# RELAY16.net
KiCad netlist of a schematic drawn in EAGLE
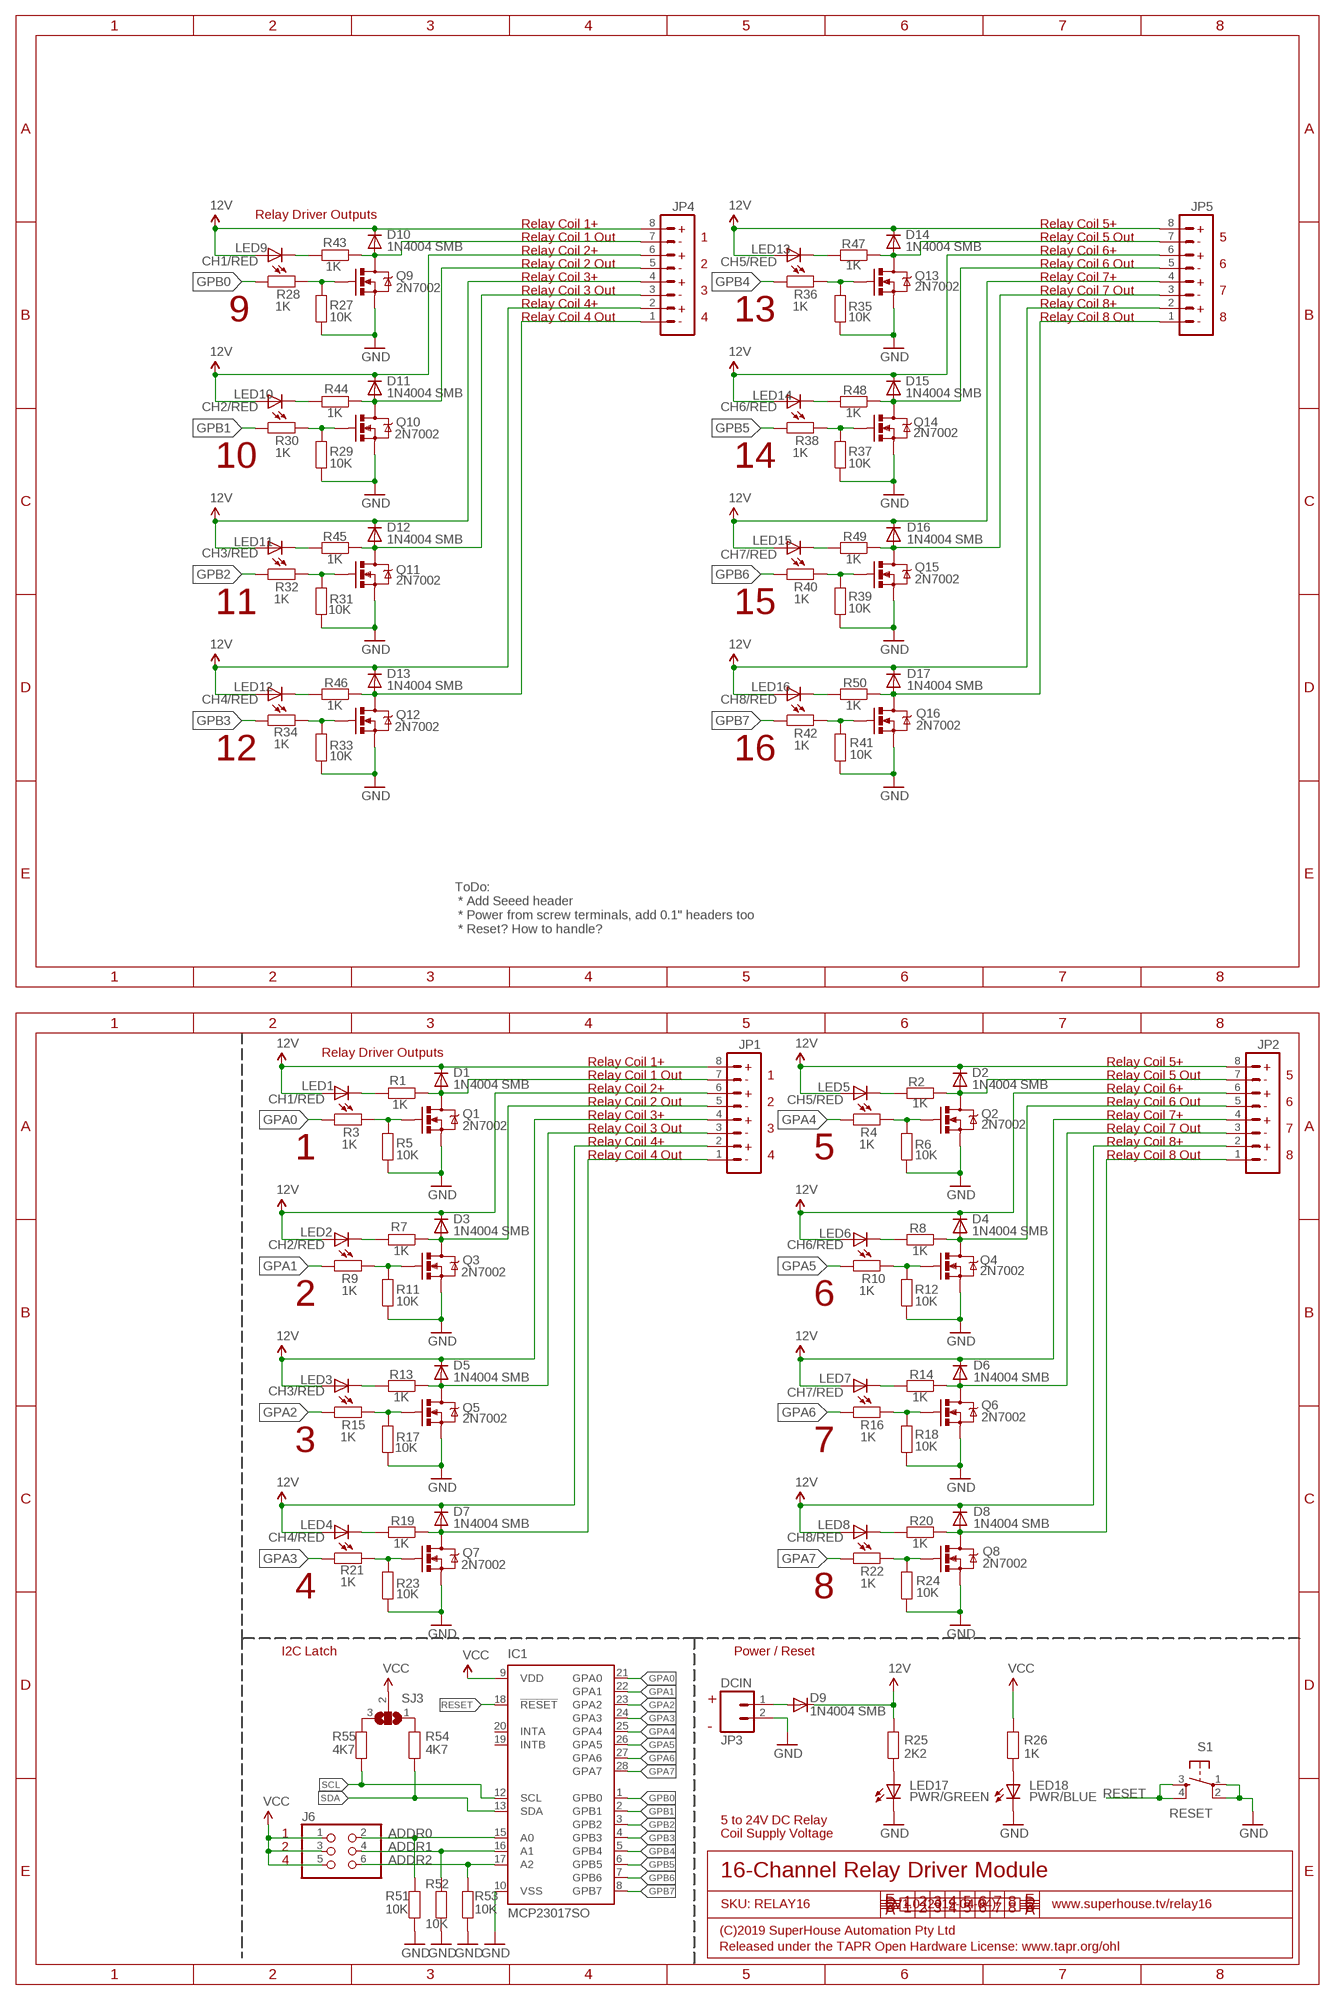
[diagram p0: schematic, sheet 1]

(export (version "E")
  (design (tool "Eeschema 10.0.6"))
  (components
    (comp (ref "D1")
      (value "1N4004 SMB")
      (footprint "eagle-import:SMB-DIODE")
      (libsource (lib "eagle-import") (part "DIODESMB"))
    )
    (comp (ref "D2")
      (value "1N4004 SMB")
      (footprint "eagle-import:SMB-DIODE")
      (libsource (lib "eagle-import") (part "DIODESMB"))
    )
    (comp (ref "D3")
      (value "1N4004 SMB")
      (footprint "eagle-import:SMB-DIODE")
      (libsource (lib "eagle-import") (part "DIODESMB"))
    )
    (comp (ref "D4")
      (value "1N4004 SMB")
      (footprint "eagle-import:SMB-DIODE")
      (libsource (lib "eagle-import") (part "DIODESMB"))
    )
    (comp (ref "D5")
      (value "1N4004 SMB")
      (footprint "eagle-import:SMB-DIODE")
      (libsource (lib "eagle-import") (part "DIODESMB"))
    )
    (comp (ref "D6")
      (value "1N4004 SMB")
      (footprint "eagle-import:SMB-DIODE")
      (libsource (lib "eagle-import") (part "DIODESMB"))
    )
    (comp (ref "D7")
      (value "1N4004 SMB")
      (footprint "eagle-import:SMB-DIODE")
      (libsource (lib "eagle-import") (part "DIODESMB"))
    )
    (comp (ref "D8")
      (value "1N4004 SMB")
      (footprint "eagle-import:SMB-DIODE")
      (libsource (lib "eagle-import") (part "DIODESMB"))
    )
    (comp (ref "D9")
      (value "1N4004 SMB")
      (footprint "eagle-import:SMB-DIODE")
      (libsource (lib "eagle-import") (part "DIODESMB"))
    )
    (comp (ref "D10")
      (value "1N4004 SMB")
      (footprint "eagle-import:SMB-DIODE")
      (libsource (lib "eagle-import") (part "DIODESMB"))
    )
    (comp (ref "D11")
      (value "1N4004 SMB")
      (footprint "eagle-import:SMB-DIODE")
      (libsource (lib "eagle-import") (part "DIODESMB"))
    )
    (comp (ref "D12")
      (value "1N4004 SMB")
      (footprint "eagle-import:SMB-DIODE")
      (libsource (lib "eagle-import") (part "DIODESMB"))
    )
    (comp (ref "D13")
      (value "1N4004 SMB")
      (footprint "eagle-import:SMB-DIODE")
      (libsource (lib "eagle-import") (part "DIODESMB"))
    )
    (comp (ref "D14")
      (value "1N4004 SMB")
      (footprint "eagle-import:SMB-DIODE")
      (libsource (lib "eagle-import") (part "DIODESMB"))
    )
    (comp (ref "D15")
      (value "1N4004 SMB")
      (footprint "eagle-import:SMB-DIODE")
      (libsource (lib "eagle-import") (part "DIODESMB"))
    )
    (comp (ref "D16")
      (value "1N4004 SMB")
      (footprint "eagle-import:SMB-DIODE")
      (libsource (lib "eagle-import") (part "DIODESMB"))
    )
    (comp (ref "D17")
      (value "1N4004 SMB")
      (footprint "eagle-import:SMB-DIODE")
      (libsource (lib "eagle-import") (part "DIODESMB"))
    )
    (comp (ref "IC1")
      (value "MCP23017SO")
      (footprint "eagle-import:SO28W")
      (libsource (lib "eagle-import") (part "MCP23017SO"))
    )
    (comp (ref "J6")
      (value "PINHD-2X3")
      (footprint "eagle-import:2X03")
      (libsource (lib "eagle-import") (part "PINHD-2X3"))
    )
    (comp (ref "JP1")
      (value "M08")
      (footprint "eagle-import:TERMINALBLOCK_3.5MM_8")
      (libsource (lib "eagle-import") (part "M08"))
    )
    (comp (ref "JP2")
      (value "M08")
      (footprint "eagle-import:TERMINALBLOCK_3.5MM_8")
      (libsource (lib "eagle-import") (part "M08"))
    )
    (comp (ref "JP3")
      (value "DCIN")
      (footprint "eagle-import:SCREWTERMINAL-3.5MM-2")
      (libsource (lib "eagle-import") (part "M023.5MM"))
    )
    (comp (ref "JP4")
      (value "M08")
      (footprint "eagle-import:TERMINALBLOCK_3.5MM_8")
      (libsource (lib "eagle-import") (part "M08"))
    )
    (comp (ref "JP5")
      (value "M08")
      (footprint "eagle-import:TERMINALBLOCK_3.5MM_8")
      (libsource (lib "eagle-import") (part "M08"))
    )
    (comp (ref "LED1")
      (value "CH1/RED")
      (footprint "eagle-import:LED-0603")
      (libsource (lib "eagle-import") (part "LED0603"))
    )
    (comp (ref "LED2")
      (value "CH2/RED")
      (footprint "eagle-import:LED-0603")
      (libsource (lib "eagle-import") (part "LED0603"))
    )
    (comp (ref "LED3")
      (value "CH3/RED")
      (footprint "eagle-import:LED-0603")
      (libsource (lib "eagle-import") (part "LED0603"))
    )
    (comp (ref "LED4")
      (value "CH4/RED")
      (footprint "eagle-import:LED-0603")
      (libsource (lib "eagle-import") (part "LED0603"))
    )
    (comp (ref "LED5")
      (value "CH5/RED")
      (footprint "eagle-import:LED-0603")
      (libsource (lib "eagle-import") (part "LED0603"))
    )
    (comp (ref "LED6")
      (value "CH6/RED")
      (footprint "eagle-import:LED-0603")
      (libsource (lib "eagle-import") (part "LED0603"))
    )
    (comp (ref "LED7")
      (value "CH7/RED")
      (footprint "eagle-import:LED-0603")
      (libsource (lib "eagle-import") (part "LED0603"))
    )
    (comp (ref "LED8")
      (value "CH8/RED")
      (footprint "eagle-import:LED-0603")
      (libsource (lib "eagle-import") (part "LED0603"))
    )
    (comp (ref "LED9")
      (value "CH1/RED")
      (footprint "eagle-import:LED-0603")
      (libsource (lib "eagle-import") (part "LED0603"))
    )
    (comp (ref "LED10")
      (value "CH2/RED")
      (footprint "eagle-import:LED-0603")
      (libsource (lib "eagle-import") (part "LED0603"))
    )
    (comp (ref "LED11")
      (value "CH3/RED")
      (footprint "eagle-import:LED-0603")
      (libsource (lib "eagle-import") (part "LED0603"))
    )
    (comp (ref "LED12")
      (value "CH4/RED")
      (footprint "eagle-import:LED-0603")
      (libsource (lib "eagle-import") (part "LED0603"))
    )
    (comp (ref "LED13")
      (value "CH5/RED")
      (footprint "eagle-import:LED-0603")
      (libsource (lib "eagle-import") (part "LED0603"))
    )
    (comp (ref "LED14")
      (value "CH6/RED")
      (footprint "eagle-import:LED-0603")
      (libsource (lib "eagle-import") (part "LED0603"))
    )
    (comp (ref "LED15")
      (value "CH7/RED")
      (footprint "eagle-import:LED-0603")
      (libsource (lib "eagle-import") (part "LED0603"))
    )
    (comp (ref "LED16")
      (value "CH8/RED")
      (footprint "eagle-import:LED-0603")
      (libsource (lib "eagle-import") (part "LED0603"))
    )
    (comp (ref "LED17")
      (value "PWR/GREEN")
      (footprint "eagle-import:LED-0603")
      (libsource (lib "eagle-import") (part "LED0603"))
    )
    (comp (ref "LED18")
      (value "PWR/BLUE")
      (footprint "eagle-import:LED-0603")
      (libsource (lib "eagle-import") (part "LED0603"))
    )
    (comp (ref "Q1")
      (value "2N7002")
      (footprint "eagle-import:SOT23-3")
      (libsource (lib "eagle-import") (part "MOSFET-NCHANNELSMD"))
    )
    (comp (ref "Q2")
      (value "2N7002")
      (footprint "eagle-import:SOT23-3")
      (libsource (lib "eagle-import") (part "MOSFET-NCHANNELSMD"))
    )
    (comp (ref "Q3")
      (value "2N7002")
      (footprint "eagle-import:SOT23-3")
      (libsource (lib "eagle-import") (part "MOSFET-NCHANNELSMD"))
    )
    (comp (ref "Q4")
      (value "2N7002")
      (footprint "eagle-import:SOT23-3")
      (libsource (lib "eagle-import") (part "MOSFET-NCHANNELSMD"))
    )
    (comp (ref "Q5")
      (value "2N7002")
      (footprint "eagle-import:SOT23-3")
      (libsource (lib "eagle-import") (part "MOSFET-NCHANNELSMD"))
    )
    (comp (ref "Q6")
      (value "2N7002")
      (footprint "eagle-import:SOT23-3")
      (libsource (lib "eagle-import") (part "MOSFET-NCHANNELSMD"))
    )
    (comp (ref "Q7")
      (value "2N7002")
      (footprint "eagle-import:SOT23-3")
      (libsource (lib "eagle-import") (part "MOSFET-NCHANNELSMD"))
    )
    (comp (ref "Q8")
      (value "2N7002")
      (footprint "eagle-import:SOT23-3")
      (libsource (lib "eagle-import") (part "MOSFET-NCHANNELSMD"))
    )
    (comp (ref "Q9")
      (value "2N7002")
      (footprint "eagle-import:SOT23-3")
      (libsource (lib "eagle-import") (part "MOSFET-NCHANNELSMD"))
    )
    (comp (ref "Q10")
      (value "2N7002")
      (footprint "eagle-import:SOT23-3")
      (libsource (lib "eagle-import") (part "MOSFET-NCHANNELSMD"))
    )
    (comp (ref "Q11")
      (value "2N7002")
      (footprint "eagle-import:SOT23-3")
      (libsource (lib "eagle-import") (part "MOSFET-NCHANNELSMD"))
    )
    (comp (ref "Q12")
      (value "2N7002")
      (footprint "eagle-import:SOT23-3")
      (libsource (lib "eagle-import") (part "MOSFET-NCHANNELSMD"))
    )
    (comp (ref "Q13")
      (value "2N7002")
      (footprint "eagle-import:SOT23-3")
      (libsource (lib "eagle-import") (part "MOSFET-NCHANNELSMD"))
    )
    (comp (ref "Q14")
      (value "2N7002")
      (footprint "eagle-import:SOT23-3")
      (libsource (lib "eagle-import") (part "MOSFET-NCHANNELSMD"))
    )
    (comp (ref "Q15")
      (value "2N7002")
      (footprint "eagle-import:SOT23-3")
      (libsource (lib "eagle-import") (part "MOSFET-NCHANNELSMD"))
    )
    (comp (ref "Q16")
      (value "2N7002")
      (footprint "eagle-import:SOT23-3")
      (libsource (lib "eagle-import") (part "MOSFET-NCHANNELSMD"))
    )
    (comp (ref "R1")
      (value "1K")
      (footprint "eagle-import:0603")
      (libsource (lib "eagle-import") (part "RESISTOR0603"))
    )
    (comp (ref "R2")
      (value "1K")
      (footprint "eagle-import:0603")
      (libsource (lib "eagle-import") (part "RESISTOR0603"))
    )
    (comp (ref "R3")
      (value "1K")
      (footprint "eagle-import:0603")
      (libsource (lib "eagle-import") (part "RESISTOR0603"))
    )
    (comp (ref "R4")
      (value "1K")
      (footprint "eagle-import:0603")
      (libsource (lib "eagle-import") (part "RESISTOR0603"))
    )
    (comp (ref "R5")
      (value "10K")
      (footprint "eagle-import:0603")
      (libsource (lib "eagle-import") (part "RESISTOR0603"))
    )
    (comp (ref "R6")
      (value "10K")
      (footprint "eagle-import:0603")
      (libsource (lib "eagle-import") (part "RESISTOR0603"))
    )
    (comp (ref "R7")
      (value "1K")
      (footprint "eagle-import:0603")
      (libsource (lib "eagle-import") (part "RESISTOR0603"))
    )
    (comp (ref "R8")
      (value "1K")
      (footprint "eagle-import:0603")
      (libsource (lib "eagle-import") (part "RESISTOR0603"))
    )
    (comp (ref "R9")
      (value "1K")
      (footprint "eagle-import:0603")
      (libsource (lib "eagle-import") (part "RESISTOR0603"))
    )
    (comp (ref "R10")
      (value "1K")
      (footprint "eagle-import:0603")
      (libsource (lib "eagle-import") (part "RESISTOR0603"))
    )
    (comp (ref "R11")
      (value "10K")
      (footprint "eagle-import:0603")
      (libsource (lib "eagle-import") (part "RESISTOR0603"))
    )
    (comp (ref "R12")
      (value "10K")
      (footprint "eagle-import:0603")
      (libsource (lib "eagle-import") (part "RESISTOR0603"))
    )
    (comp (ref "R13")
      (value "1K")
      (footprint "eagle-import:0603")
      (libsource (lib "eagle-import") (part "RESISTOR0603"))
    )
    (comp (ref "R14")
      (value "1K")
      (footprint "eagle-import:0603")
      (libsource (lib "eagle-import") (part "RESISTOR0603"))
    )
    (comp (ref "R15")
      (value "1K")
      (footprint "eagle-import:0603")
      (libsource (lib "eagle-import") (part "RESISTOR0603"))
    )
    (comp (ref "R16")
      (value "1K")
      (footprint "eagle-import:0603")
      (libsource (lib "eagle-import") (part "RESISTOR0603"))
    )
    (comp (ref "R17")
      (value "10K")
      (footprint "eagle-import:0603")
      (libsource (lib "eagle-import") (part "RESISTOR0603"))
    )
    (comp (ref "R18")
      (value "10K")
      (footprint "eagle-import:0603")
      (libsource (lib "eagle-import") (part "RESISTOR0603"))
    )
    (comp (ref "R19")
      (value "1K")
      (footprint "eagle-import:0603")
      (libsource (lib "eagle-import") (part "RESISTOR0603"))
    )
    (comp (ref "R20")
      (value "1K")
      (footprint "eagle-import:0603")
      (libsource (lib "eagle-import") (part "RESISTOR0603"))
    )
    (comp (ref "R21")
      (value "1K")
      (footprint "eagle-import:0603")
      (libsource (lib "eagle-import") (part "RESISTOR0603"))
    )
    (comp (ref "R22")
      (value "1K")
      (footprint "eagle-import:0603")
      (libsource (lib "eagle-import") (part "RESISTOR0603"))
    )
    (comp (ref "R23")
      (value "10K")
      (footprint "eagle-import:0603")
      (libsource (lib "eagle-import") (part "RESISTOR0603"))
    )
    (comp (ref "R24")
      (value "10K")
      (footprint "eagle-import:0603")
      (libsource (lib "eagle-import") (part "RESISTOR0603"))
    )
    (comp (ref "R25")
      (value "2K2")
      (footprint "eagle-import:0603")
      (libsource (lib "eagle-import") (part "RESISTOR0603"))
    )
    (comp (ref "R26")
      (value "1K")
      (footprint "eagle-import:0603")
      (libsource (lib "eagle-import") (part "RESISTOR0603"))
    )
    (comp (ref "R27")
      (value "10K")
      (footprint "eagle-import:0603")
      (libsource (lib "eagle-import") (part "RESISTOR0603"))
    )
    (comp (ref "R28")
      (value "1K")
      (footprint "eagle-import:0603")
      (libsource (lib "eagle-import") (part "RESISTOR0603"))
    )
    (comp (ref "R29")
      (value "10K")
      (footprint "eagle-import:0603")
      (libsource (lib "eagle-import") (part "RESISTOR0603"))
    )
    (comp (ref "R30")
      (value "1K")
      (footprint "eagle-import:0603")
      (libsource (lib "eagle-import") (part "RESISTOR0603"))
    )
    (comp (ref "R31")
      (value "10K")
      (footprint "eagle-import:0603")
      (libsource (lib "eagle-import") (part "RESISTOR0603"))
    )
    (comp (ref "R32")
      (value "1K")
      (footprint "eagle-import:0603")
      (libsource (lib "eagle-import") (part "RESISTOR0603"))
    )
    (comp (ref "R33")
      (value "10K")
      (footprint "eagle-import:0603")
      (libsource (lib "eagle-import") (part "RESISTOR0603"))
    )
    (comp (ref "R34")
      (value "1K")
      (footprint "eagle-import:0603")
      (libsource (lib "eagle-import") (part "RESISTOR0603"))
    )
    (comp (ref "R35")
      (value "10K")
      (footprint "eagle-import:0603")
      (libsource (lib "eagle-import") (part "RESISTOR0603"))
    )
    (comp (ref "R36")
      (value "1K")
      (footprint "eagle-import:0603")
      (libsource (lib "eagle-import") (part "RESISTOR0603"))
    )
    (comp (ref "R37")
      (value "10K")
      (footprint "eagle-import:0603")
      (libsource (lib "eagle-import") (part "RESISTOR0603"))
    )
    (comp (ref "R38")
      (value "1K")
      (footprint "eagle-import:0603")
      (libsource (lib "eagle-import") (part "RESISTOR0603"))
    )
    (comp (ref "R39")
      (value "10K")
      (footprint "eagle-import:0603")
      (libsource (lib "eagle-import") (part "RESISTOR0603"))
    )
    (comp (ref "R40")
      (value "1K")
      (footprint "eagle-import:0603")
      (libsource (lib "eagle-import") (part "RESISTOR0603"))
    )
    (comp (ref "R41")
      (value "10K")
      (footprint "eagle-import:0603")
      (libsource (lib "eagle-import") (part "RESISTOR0603"))
    )
    (comp (ref "R42")
      (value "1K")
      (footprint "eagle-import:0603")
      (libsource (lib "eagle-import") (part "RESISTOR0603"))
    )
    (comp (ref "R43")
      (value "1K")
      (footprint "eagle-import:0603")
      (libsource (lib "eagle-import") (part "RESISTOR0603"))
    )
    (comp (ref "R44")
      (value "1K")
      (footprint "eagle-import:0603")
      (libsource (lib "eagle-import") (part "RESISTOR0603"))
    )
    (comp (ref "R45")
      (value "1K")
      (footprint "eagle-import:0603")
      (libsource (lib "eagle-import") (part "RESISTOR0603"))
    )
    (comp (ref "R46")
      (value "1K")
      (footprint "eagle-import:0603")
      (libsource (lib "eagle-import") (part "RESISTOR0603"))
    )
    (comp (ref "R47")
      (value "1K")
      (footprint "eagle-import:0603")
      (libsource (lib "eagle-import") (part "RESISTOR0603"))
    )
    (comp (ref "R48")
      (value "1K")
      (footprint "eagle-import:0603")
      (libsource (lib "eagle-import") (part "RESISTOR0603"))
    )
    (comp (ref "R49")
      (value "1K")
      (footprint "eagle-import:0603")
      (libsource (lib "eagle-import") (part "RESISTOR0603"))
    )
    (comp (ref "R50")
      (value "1K")
      (footprint "eagle-import:0603")
      (libsource (lib "eagle-import") (part "RESISTOR0603"))
    )
    (comp (ref "R51")
      (value "10K")
      (footprint "eagle-import:0603")
      (libsource (lib "eagle-import") (part "RESISTOR0603"))
    )
    (comp (ref "R52")
      (value "10K")
      (footprint "eagle-import:0603")
      (libsource (lib "eagle-import") (part "RESISTOR0603"))
    )
    (comp (ref "R53")
      (value "10K")
      (footprint "eagle-import:0603")
      (libsource (lib "eagle-import") (part "RESISTOR0603"))
    )
    (comp (ref "R54")
      (value "4K7")
      (footprint "eagle-import:0603")
      (libsource (lib "eagle-import") (part "RESISTOR0603"))
    )
    (comp (ref "R55")
      (value "4K7")
      (footprint "eagle-import:0603")
      (libsource (lib "eagle-import") (part "RESISTOR0603"))
    )
    (comp (ref "S1")
      (value "RESET")
      (footprint "eagle-import:TACTILE_SWITCH_SMD")
      (libsource (lib "eagle-import") (part "TAC_SWITCHSMD"))
    )
    (comp (ref "SJ3")
      (value "SJ2W")
      (footprint "eagle-import:SJ_2")
      (libsource (lib "eagle-import") (part "SJ2W"))
    )
  )
  (nets
    (net (code "1") (name "/ADDR0") (class "Default")
      (node (ref "IC1") (pin "15") (pinfunction "A0_15") (pintype "input"))
      (node (ref "J6") (pin "2") (pinfunction "2_2") (pintype "passive"))
      (node (ref "R51") (pin "2") (pinfunction "2_2") (pintype "passive"))
    )
    (net (code "2") (name "/ADDR1") (class "Default")
      (node (ref "IC1") (pin "16") (pinfunction "A1_16") (pintype "input"))
      (node (ref "J6") (pin "4") (pinfunction "4_4") (pintype "passive"))
      (node (ref "R52") (pin "2") (pinfunction "2_2") (pintype "passive"))
    )
    (net (code "3") (name "/ADDR2") (class "Default")
      (node (ref "IC1") (pin "17") (pinfunction "A2_17") (pintype "input"))
      (node (ref "J6") (pin "6") (pinfunction "6_6") (pintype "passive"))
      (node (ref "R53") (pin "2") (pinfunction "2_2") (pintype "passive"))
    )
    (net (code "4") (name "12V") (class "Default")
      (node (ref "D1") (pin "C") (pinfunction "C_C") (pintype "passive"))
      (node (ref "D10") (pin "C") (pinfunction "C_C") (pintype "passive"))
      (node (ref "D11") (pin "C") (pinfunction "C_C") (pintype "passive"))
      (node (ref "D12") (pin "C") (pinfunction "C_C") (pintype "passive"))
      (node (ref "D13") (pin "C") (pinfunction "C_C") (pintype "passive"))
      (node (ref "D14") (pin "C") (pinfunction "C_C") (pintype "passive"))
      (node (ref "D15") (pin "C") (pinfunction "C_C") (pintype "passive"))
      (node (ref "D16") (pin "C") (pinfunction "C_C") (pintype "passive"))
      (node (ref "D17") (pin "C") (pinfunction "C_C") (pintype "passive"))
      (node (ref "D2") (pin "C") (pinfunction "C_C") (pintype "passive"))
      (node (ref "D3") (pin "C") (pinfunction "C_C") (pintype "passive"))
      (node (ref "D4") (pin "C") (pinfunction "C_C") (pintype "passive"))
      (node (ref "D5") (pin "C") (pinfunction "C_C") (pintype "passive"))
      (node (ref "D6") (pin "C") (pinfunction "C_C") (pintype "passive"))
      (node (ref "D7") (pin "C") (pinfunction "C_C") (pintype "passive"))
      (node (ref "D8") (pin "C") (pinfunction "C_C") (pintype "passive"))
      (node (ref "D9") (pin "C") (pinfunction "C_C") (pintype "passive"))
      (node (ref "JP1") (pin "2") (pinfunction "2_2") (pintype "passive"))
      (node (ref "JP1") (pin "4") (pinfunction "4_4") (pintype "passive"))
      (node (ref "JP1") (pin "6") (pinfunction "6_6") (pintype "passive"))
      (node (ref "JP1") (pin "8") (pinfunction "8_8") (pintype "passive"))
      (node (ref "JP2") (pin "2") (pinfunction "2_2") (pintype "passive"))
      (node (ref "JP2") (pin "4") (pinfunction "4_4") (pintype "passive"))
      (node (ref "JP2") (pin "6") (pinfunction "6_6") (pintype "passive"))
      (node (ref "JP2") (pin "8") (pinfunction "8_8") (pintype "passive"))
      (node (ref "JP4") (pin "2") (pinfunction "2_2") (pintype "passive"))
      (node (ref "JP4") (pin "4") (pinfunction "4_4") (pintype "passive"))
      (node (ref "JP4") (pin "6") (pinfunction "6_6") (pintype "passive"))
      (node (ref "JP4") (pin "8") (pinfunction "8_8") (pintype "passive"))
      (node (ref "JP5") (pin "2") (pinfunction "2_2") (pintype "passive"))
      (node (ref "JP5") (pin "4") (pinfunction "4_4") (pintype "passive"))
      (node (ref "JP5") (pin "6") (pinfunction "6_6") (pintype "passive"))
      (node (ref "JP5") (pin "8") (pinfunction "8_8") (pintype "passive"))
      (node (ref "LED1") (pin "A") (pinfunction "A_A") (pintype "passive"))
      (node (ref "LED10") (pin "A") (pinfunction "A_A") (pintype "passive"))
      (node (ref "LED11") (pin "A") (pinfunction "A_A") (pintype "passive"))
      (node (ref "LED12") (pin "A") (pinfunction "A_A") (pintype "passive"))
      (node (ref "LED13") (pin "A") (pinfunction "A_A") (pintype "passive"))
      (node (ref "LED14") (pin "A") (pinfunction "A_A") (pintype "passive"))
      (node (ref "LED15") (pin "A") (pinfunction "A_A") (pintype "passive"))
      (node (ref "LED16") (pin "A") (pinfunction "A_A") (pintype "passive"))
      (node (ref "LED2") (pin "A") (pinfunction "A_A") (pintype "passive"))
      (node (ref "LED3") (pin "A") (pinfunction "A_A") (pintype "passive"))
      (node (ref "LED4") (pin "A") (pinfunction "A_A") (pintype "passive"))
      (node (ref "LED5") (pin "A") (pinfunction "A_A") (pintype "passive"))
      (node (ref "LED6") (pin "A") (pinfunction "A_A") (pintype "passive"))
      (node (ref "LED7") (pin "A") (pinfunction "A_A") (pintype "passive"))
      (node (ref "LED8") (pin "A") (pinfunction "A_A") (pintype "passive"))
      (node (ref "LED9") (pin "A") (pinfunction "A_A") (pintype "passive"))
      (node (ref "R25") (pin "2") (pinfunction "2_2") (pintype "passive"))
    )
    (net (code "5") (name "GND") (class "Default")
      (node (ref "IC1") (pin "10") (pinfunction "VSS_10") (pintype "power_in"))
      (node (ref "JP3") (pin "2") (pinfunction "2_2") (pintype "passive"))
      (node (ref "LED17") (pin "C") (pinfunction "C_C") (pintype "passive"))
      (node (ref "LED18") (pin "C") (pinfunction "C_C") (pintype "passive"))
      (node (ref "Q1") (pin "2") (pinfunction "S_2") (pintype "passive"))
      (node (ref "Q10") (pin "2") (pinfunction "S_2") (pintype "passive"))
      (node (ref "Q11") (pin "2") (pinfunction "S_2") (pintype "passive"))
      (node (ref "Q12") (pin "2") (pinfunction "S_2") (pintype "passive"))
      (node (ref "Q13") (pin "2") (pinfunction "S_2") (pintype "passive"))
      (node (ref "Q14") (pin "2") (pinfunction "S_2") (pintype "passive"))
      (node (ref "Q15") (pin "2") (pinfunction "S_2") (pintype "passive"))
      (node (ref "Q16") (pin "2") (pinfunction "S_2") (pintype "passive"))
      (node (ref "Q2") (pin "2") (pinfunction "S_2") (pintype "passive"))
      (node (ref "Q3") (pin "2") (pinfunction "S_2") (pintype "passive"))
      (node (ref "Q4") (pin "2") (pinfunction "S_2") (pintype "passive"))
      (node (ref "Q5") (pin "2") (pinfunction "S_2") (pintype "passive"))
      (node (ref "Q6") (pin "2") (pinfunction "S_2") (pintype "passive"))
      (node (ref "Q7") (pin "2") (pinfunction "S_2") (pintype "passive"))
      (node (ref "Q8") (pin "2") (pinfunction "S_2") (pintype "passive"))
      (node (ref "Q9") (pin "2") (pinfunction "S_2") (pintype "passive"))
      (node (ref "R11") (pin "1") (pinfunction "1_1") (pintype "passive"))
      (node (ref "R12") (pin "1") (pinfunction "1_1") (pintype "passive"))
      (node (ref "R17") (pin "1") (pinfunction "1_1") (pintype "passive"))
      (node (ref "R18") (pin "1") (pinfunction "1_1") (pintype "passive"))
      (node (ref "R23") (pin "1") (pinfunction "1_1") (pintype "passive"))
      (node (ref "R24") (pin "1") (pinfunction "1_1") (pintype "passive"))
      (node (ref "R27") (pin "1") (pinfunction "1_1") (pintype "passive"))
      (node (ref "R29") (pin "1") (pinfunction "1_1") (pintype "passive"))
      (node (ref "R31") (pin "1") (pinfunction "1_1") (pintype "passive"))
      (node (ref "R33") (pin "1") (pinfunction "1_1") (pintype "passive"))
      (node (ref "R35") (pin "1") (pinfunction "1_1") (pintype "passive"))
      (node (ref "R37") (pin "1") (pinfunction "1_1") (pintype "passive"))
      (node (ref "R39") (pin "1") (pinfunction "1_1") (pintype "passive"))
      (node (ref "R41") (pin "1") (pinfunction "1_1") (pintype "passive"))
      (node (ref "R5") (pin "1") (pinfunction "1_1") (pintype "passive"))
      (node (ref "R51") (pin "1") (pinfunction "1_1") (pintype "passive"))
      (node (ref "R52") (pin "1") (pinfunction "1_1") (pintype "passive"))
      (node (ref "R53") (pin "1") (pinfunction "1_1") (pintype "passive"))
      (node (ref "R6") (pin "1") (pinfunction "1_1") (pintype "passive"))
      (node (ref "S1") (pin "1") (pinfunction "1_1") (pintype "passive"))
      (node (ref "S1") (pin "2") (pinfunction "2_2") (pintype "passive"))
    )
    (net (code "6") (name "GPA0") (class "Default")
      (node (ref "IC1") (pin "21") (pinfunction "GPA0_21") (pintype "bidirectional"))
      (node (ref "R3") (pin "2") (pinfunction "2_2") (pintype "passive"))
    )
    (net (code "7") (name "GPA1") (class "Default")
      (node (ref "IC1") (pin "22") (pinfunction "GPA1_22") (pintype "bidirectional"))
      (node (ref "R9") (pin "2") (pinfunction "2_2") (pintype "passive"))
    )
    (net (code "8") (name "GPA2") (class "Default")
      (node (ref "IC1") (pin "23") (pinfunction "GPA2_23") (pintype "bidirectional"))
      (node (ref "R15") (pin "2") (pinfunction "2_2") (pintype "passive"))
    )
    (net (code "9") (name "GPA3") (class "Default")
      (node (ref "IC1") (pin "24") (pinfunction "GPA3_24") (pintype "bidirectional"))
      (node (ref "R21") (pin "2") (pinfunction "2_2") (pintype "passive"))
    )
    (net (code "10") (name "GPA4") (class "Default")
      (node (ref "IC1") (pin "25") (pinfunction "GPA4_25") (pintype "bidirectional"))
      (node (ref "R4") (pin "2") (pinfunction "2_2") (pintype "passive"))
    )
    (net (code "11") (name "GPA5") (class "Default")
      (node (ref "IC1") (pin "26") (pinfunction "GPA5_26") (pintype "bidirectional"))
      (node (ref "R10") (pin "2") (pinfunction "2_2") (pintype "passive"))
    )
    (net (code "12") (name "GPA6") (class "Default")
      (node (ref "IC1") (pin "27") (pinfunction "GPA6_27") (pintype "bidirectional"))
      (node (ref "R16") (pin "2") (pinfunction "2_2") (pintype "passive"))
    )
    (net (code "13") (name "GPA7") (class "Default")
      (node (ref "IC1") (pin "28") (pinfunction "GPA7_28") (pintype "bidirectional"))
      (node (ref "R22") (pin "2") (pinfunction "2_2") (pintype "passive"))
    )
    (net (code "14") (name "GPB0") (class "Default")
      (node (ref "IC1") (pin "1") (pinfunction "GPB0_1") (pintype "bidirectional"))
      (node (ref "R28") (pin "2") (pinfunction "2_2") (pintype "passive"))
    )
    (net (code "15") (name "GPB1") (class "Default")
      (node (ref "IC1") (pin "2") (pinfunction "GPB1_2") (pintype "bidirectional"))
      (node (ref "R30") (pin "2") (pinfunction "2_2") (pintype "passive"))
    )
    (net (code "16") (name "GPB2") (class "Default")
      (node (ref "IC1") (pin "3") (pinfunction "GPB2_3") (pintype "bidirectional"))
      (node (ref "R32") (pin "2") (pinfunction "2_2") (pintype "passive"))
    )
    (net (code "17") (name "GPB3") (class "Default")
      (node (ref "IC1") (pin "4") (pinfunction "GPB3_4") (pintype "bidirectional"))
      (node (ref "R34") (pin "2") (pinfunction "2_2") (pintype "passive"))
    )
    (net (code "18") (name "GPB4") (class "Default")
      (node (ref "IC1") (pin "5") (pinfunction "GPB4_5") (pintype "bidirectional"))
      (node (ref "R36") (pin "2") (pinfunction "2_2") (pintype "passive"))
    )
    (net (code "19") (name "GPB5") (class "Default")
      (node (ref "IC1") (pin "6") (pinfunction "GPB5_6") (pintype "bidirectional"))
      (node (ref "R38") (pin "2") (pinfunction "2_2") (pintype "passive"))
    )
    (net (code "20") (name "GPB6") (class "Default")
      (node (ref "IC1") (pin "7") (pinfunction "GPB6_7") (pintype "bidirectional"))
      (node (ref "R40") (pin "2") (pinfunction "2_2") (pintype "passive"))
    )
    (net (code "21") (name "GPB7") (class "Default")
      (node (ref "IC1") (pin "8") (pinfunction "GPB7_8") (pintype "bidirectional"))
      (node (ref "R42") (pin "2") (pinfunction "2_2") (pintype "passive"))
    )
    (net (code "22") (name "Net-(D9-PadA)") (class "Default")
      (node (ref "D9") (pin "A") (pinfunction "A_A") (pintype "passive"))
      (node (ref "JP3") (pin "1") (pinfunction "1_1") (pintype "passive"))
    )
    (net (code "23") (name "Net-(LED1-PadC)") (class "Default")
      (node (ref "LED1") (pin "C") (pinfunction "C_C") (pintype "passive"))
      (node (ref "R1") (pin "1") (pinfunction "1_1") (pintype "passive"))
    )
    (net (code "24") (name "Net-(LED2-PadC)") (class "Default")
      (node (ref "LED2") (pin "C") (pinfunction "C_C") (pintype "passive"))
      (node (ref "R7") (pin "1") (pinfunction "1_1") (pintype "passive"))
    )
    (net (code "25") (name "Net-(LED3-PadC)") (class "Default")
      (node (ref "LED3") (pin "C") (pinfunction "C_C") (pintype "passive"))
      (node (ref "R13") (pin "1") (pinfunction "1_1") (pintype "passive"))
    )
    (net (code "26") (name "Net-(LED4-PadC)") (class "Default")
      (node (ref "LED4") (pin "C") (pinfunction "C_C") (pintype "passive"))
      (node (ref "R19") (pin "1") (pinfunction "1_1") (pintype "passive"))
    )
    (net (code "27") (name "Net-(LED5-PadC)") (class "Default")
      (node (ref "LED5") (pin "C") (pinfunction "C_C") (pintype "passive"))
      (node (ref "R2") (pin "1") (pinfunction "1_1") (pintype "passive"))
    )
    (net (code "28") (name "Net-(LED6-PadC)") (class "Default")
      (node (ref "LED6") (pin "C") (pinfunction "C_C") (pintype "passive"))
      (node (ref "R8") (pin "1") (pinfunction "1_1") (pintype "passive"))
    )
    (net (code "29") (name "Net-(LED7-PadC)") (class "Default")
      (node (ref "LED7") (pin "C") (pinfunction "C_C") (pintype "passive"))
      (node (ref "R14") (pin "1") (pinfunction "1_1") (pintype "passive"))
    )
    (net (code "30") (name "Net-(LED8-PadC)") (class "Default")
      (node (ref "LED8") (pin "C") (pinfunction "C_C") (pintype "passive"))
      (node (ref "R20") (pin "1") (pinfunction "1_1") (pintype "passive"))
    )
    (net (code "31") (name "Net-(LED9-PadC)") (class "Default")
      (node (ref "LED9") (pin "C") (pinfunction "C_C") (pintype "passive"))
      (node (ref "R43") (pin "1") (pinfunction "1_1") (pintype "passive"))
    )
    (net (code "32") (name "Net-(LED10-PadC)") (class "Default")
      (node (ref "LED10") (pin "C") (pinfunction "C_C") (pintype "passive"))
      (node (ref "R44") (pin "1") (pinfunction "1_1") (pintype "passive"))
    )
    (net (code "33") (name "Net-(LED11-PadC)") (class "Default")
      (node (ref "LED11") (pin "C") (pinfunction "C_C") (pintype "passive"))
      (node (ref "R45") (pin "1") (pinfunction "1_1") (pintype "passive"))
    )
    (net (code "34") (name "Net-(LED12-PadC)") (class "Default")
      (node (ref "LED12") (pin "C") (pinfunction "C_C") (pintype "passive"))
      (node (ref "R46") (pin "1") (pinfunction "1_1") (pintype "passive"))
    )
    (net (code "35") (name "Net-(LED13-PadC)") (class "Default")
      (node (ref "LED13") (pin "C") (pinfunction "C_C") (pintype "passive"))
      (node (ref "R47") (pin "1") (pinfunction "1_1") (pintype "passive"))
    )
    (net (code "36") (name "Net-(LED14-PadC)") (class "Default")
      (node (ref "LED14") (pin "C") (pinfunction "C_C") (pintype "passive"))
      (node (ref "R48") (pin "1") (pinfunction "1_1") (pintype "passive"))
    )
    (net (code "37") (name "Net-(LED15-PadC)") (class "Default")
      (node (ref "LED15") (pin "C") (pinfunction "C_C") (pintype "passive"))
      (node (ref "R49") (pin "1") (pinfunction "1_1") (pintype "passive"))
    )
    (net (code "38") (name "Net-(LED16-PadC)") (class "Default")
      (node (ref "LED16") (pin "C") (pinfunction "C_C") (pintype "passive"))
      (node (ref "R50") (pin "1") (pinfunction "1_1") (pintype "passive"))
    )
    (net (code "39") (name "Net-(LED17-PadA)") (class "Default")
      (node (ref "LED17") (pin "A") (pinfunction "A_A") (pintype "passive"))
      (node (ref "R25") (pin "1") (pinfunction "1_1") (pintype "passive"))
    )
    (net (code "40") (name "Net-(LED18-PadA)") (class "Default")
      (node (ref "LED18") (pin "A") (pinfunction "A_A") (pintype "passive"))
      (node (ref "R26") (pin "1") (pinfunction "1_1") (pintype "passive"))
    )
    (net (code "41") (name "Net-(Q1-D)") (class "Default")
      (node (ref "D1") (pin "A") (pinfunction "A_A") (pintype "passive"))
      (node (ref "JP1") (pin "7") (pinfunction "7_7") (pintype "passive"))
      (node (ref "Q1") (pin "3") (pinfunction "D_3") (pintype "passive"))
      (node (ref "R1") (pin "2") (pinfunction "2_2") (pintype "passive"))
    )
    (net (code "42") (name "Net-(Q1-G)") (class "Default")
      (node (ref "Q1") (pin "1") (pinfunction "G_1") (pintype "passive"))
      (node (ref "R3") (pin "1") (pinfunction "1_1") (pintype "passive"))
      (node (ref "R5") (pin "2") (pinfunction "2_2") (pintype "passive"))
    )
    (net (code "43") (name "Net-(Q2-D)") (class "Default")
      (node (ref "D2") (pin "A") (pinfunction "A_A") (pintype "passive"))
      (node (ref "JP2") (pin "7") (pinfunction "7_7") (pintype "passive"))
      (node (ref "Q2") (pin "3") (pinfunction "D_3") (pintype "passive"))
      (node (ref "R2") (pin "2") (pinfunction "2_2") (pintype "passive"))
    )
    (net (code "44") (name "Net-(Q2-G)") (class "Default")
      (node (ref "Q2") (pin "1") (pinfunction "G_1") (pintype "passive"))
      (node (ref "R4") (pin "1") (pinfunction "1_1") (pintype "passive"))
      (node (ref "R6") (pin "2") (pinfunction "2_2") (pintype "passive"))
    )
    (net (code "45") (name "Net-(Q3-D)") (class "Default")
      (node (ref "D3") (pin "A") (pinfunction "A_A") (pintype "passive"))
      (node (ref "JP1") (pin "5") (pinfunction "5_5") (pintype "passive"))
      (node (ref "Q3") (pin "3") (pinfunction "D_3") (pintype "passive"))
      (node (ref "R7") (pin "2") (pinfunction "2_2") (pintype "passive"))
    )
    (net (code "46") (name "Net-(Q3-G)") (class "Default")
      (node (ref "Q3") (pin "1") (pinfunction "G_1") (pintype "passive"))
      (node (ref "R11") (pin "2") (pinfunction "2_2") (pintype "passive"))
      (node (ref "R9") (pin "1") (pinfunction "1_1") (pintype "passive"))
    )
    (net (code "47") (name "Net-(Q4-D)") (class "Default")
      (node (ref "D4") (pin "A") (pinfunction "A_A") (pintype "passive"))
      (node (ref "JP2") (pin "5") (pinfunction "5_5") (pintype "passive"))
      (node (ref "Q4") (pin "3") (pinfunction "D_3") (pintype "passive"))
      (node (ref "R8") (pin "2") (pinfunction "2_2") (pintype "passive"))
    )
    (net (code "48") (name "Net-(Q4-G)") (class "Default")
      (node (ref "Q4") (pin "1") (pinfunction "G_1") (pintype "passive"))
      (node (ref "R10") (pin "1") (pinfunction "1_1") (pintype "passive"))
      (node (ref "R12") (pin "2") (pinfunction "2_2") (pintype "passive"))
    )
    (net (code "49") (name "Net-(Q5-D)") (class "Default")
      (node (ref "D5") (pin "A") (pinfunction "A_A") (pintype "passive"))
      (node (ref "JP1") (pin "3") (pinfunction "3_3") (pintype "passive"))
      (node (ref "Q5") (pin "3") (pinfunction "D_3") (pintype "passive"))
      (node (ref "R13") (pin "2") (pinfunction "2_2") (pintype "passive"))
    )
    (net (code "50") (name "Net-(Q5-G)") (class "Default")
      (node (ref "Q5") (pin "1") (pinfunction "G_1") (pintype "passive"))
      (node (ref "R15") (pin "1") (pinfunction "1_1") (pintype "passive"))
      (node (ref "R17") (pin "2") (pinfunction "2_2") (pintype "passive"))
    )
    (net (code "51") (name "Net-(Q6-D)") (class "Default")
      (node (ref "D6") (pin "A") (pinfunction "A_A") (pintype "passive"))
      (node (ref "JP2") (pin "3") (pinfunction "3_3") (pintype "passive"))
      (node (ref "Q6") (pin "3") (pinfunction "D_3") (pintype "passive"))
      (node (ref "R14") (pin "2") (pinfunction "2_2") (pintype "passive"))
    )
    (net (code "52") (name "Net-(Q6-G)") (class "Default")
      (node (ref "Q6") (pin "1") (pinfunction "G_1") (pintype "passive"))
      (node (ref "R16") (pin "1") (pinfunction "1_1") (pintype "passive"))
      (node (ref "R18") (pin "2") (pinfunction "2_2") (pintype "passive"))
    )
    (net (code "53") (name "Net-(Q7-D)") (class "Default")
      (node (ref "D7") (pin "A") (pinfunction "A_A") (pintype "passive"))
      (node (ref "JP1") (pin "1") (pinfunction "1_1") (pintype "passive"))
      (node (ref "Q7") (pin "3") (pinfunction "D_3") (pintype "passive"))
      (node (ref "R19") (pin "2") (pinfunction "2_2") (pintype "passive"))
    )
    (net (code "54") (name "Net-(Q7-G)") (class "Default")
      (node (ref "Q7") (pin "1") (pinfunction "G_1") (pintype "passive"))
      (node (ref "R21") (pin "1") (pinfunction "1_1") (pintype "passive"))
      (node (ref "R23") (pin "2") (pinfunction "2_2") (pintype "passive"))
    )
    (net (code "55") (name "Net-(Q8-D)") (class "Default")
      (node (ref "D8") (pin "A") (pinfunction "A_A") (pintype "passive"))
      (node (ref "JP2") (pin "1") (pinfunction "1_1") (pintype "passive"))
      (node (ref "Q8") (pin "3") (pinfunction "D_3") (pintype "passive"))
      (node (ref "R20") (pin "2") (pinfunction "2_2") (pintype "passive"))
    )
    (net (code "56") (name "Net-(Q8-G)") (class "Default")
      (node (ref "Q8") (pin "1") (pinfunction "G_1") (pintype "passive"))
      (node (ref "R22") (pin "1") (pinfunction "1_1") (pintype "passive"))
      (node (ref "R24") (pin "2") (pinfunction "2_2") (pintype "passive"))
    )
    (net (code "57") (name "Net-(Q9-D)") (class "Default")
      (node (ref "D10") (pin "A") (pinfunction "A_A") (pintype "passive"))
      (node (ref "JP4") (pin "7") (pinfunction "7_7") (pintype "passive"))
      (node (ref "Q9") (pin "3") (pinfunction "D_3") (pintype "passive"))
      (node (ref "R43") (pin "2") (pinfunction "2_2") (pintype "passive"))
    )
    (net (code "58") (name "Net-(Q9-G)") (class "Default")
      (node (ref "Q9") (pin "1") (pinfunction "G_1") (pintype "passive"))
      (node (ref "R27") (pin "2") (pinfunction "2_2") (pintype "passive"))
      (node (ref "R28") (pin "1") (pinfunction "1_1") (pintype "passive"))
    )
    (net (code "59") (name "Net-(Q10-D)") (class "Default")
      (node (ref "D11") (pin "A") (pinfunction "A_A") (pintype "passive"))
      (node (ref "JP4") (pin "5") (pinfunction "5_5") (pintype "passive"))
      (node (ref "Q10") (pin "3") (pinfunction "D_3") (pintype "passive"))
      (node (ref "R44") (pin "2") (pinfunction "2_2") (pintype "passive"))
    )
    (net (code "60") (name "Net-(Q10-G)") (class "Default")
      (node (ref "Q10") (pin "1") (pinfunction "G_1") (pintype "passive"))
      (node (ref "R29") (pin "2") (pinfunction "2_2") (pintype "passive"))
      (node (ref "R30") (pin "1") (pinfunction "1_1") (pintype "passive"))
    )
    (net (code "61") (name "Net-(Q11-D)") (class "Default")
      (node (ref "D12") (pin "A") (pinfunction "A_A") (pintype "passive"))
      (node (ref "JP4") (pin "3") (pinfunction "3_3") (pintype "passive"))
      (node (ref "Q11") (pin "3") (pinfunction "D_3") (pintype "passive"))
      (node (ref "R45") (pin "2") (pinfunction "2_2") (pintype "passive"))
    )
    (net (code "62") (name "Net-(Q11-G)") (class "Default")
      (node (ref "Q11") (pin "1") (pinfunction "G_1") (pintype "passive"))
      (node (ref "R31") (pin "2") (pinfunction "2_2") (pintype "passive"))
      (node (ref "R32") (pin "1") (pinfunction "1_1") (pintype "passive"))
    )
    (net (code "63") (name "Net-(Q12-D)") (class "Default")
      (node (ref "D13") (pin "A") (pinfunction "A_A") (pintype "passive"))
      (node (ref "JP4") (pin "1") (pinfunction "1_1") (pintype "passive"))
      (node (ref "Q12") (pin "3") (pinfunction "D_3") (pintype "passive"))
      (node (ref "R46") (pin "2") (pinfunction "2_2") (pintype "passive"))
    )
    (net (code "64") (name "Net-(Q12-G)") (class "Default")
      (node (ref "Q12") (pin "1") (pinfunction "G_1") (pintype "passive"))
      (node (ref "R33") (pin "2") (pinfunction "2_2") (pintype "passive"))
      (node (ref "R34") (pin "1") (pinfunction "1_1") (pintype "passive"))
    )
    (net (code "65") (name "Net-(Q13-D)") (class "Default")
      (node (ref "D14") (pin "A") (pinfunction "A_A") (pintype "passive"))
      (node (ref "JP5") (pin "7") (pinfunction "7_7") (pintype "passive"))
      (node (ref "Q13") (pin "3") (pinfunction "D_3") (pintype "passive"))
      (node (ref "R47") (pin "2") (pinfunction "2_2") (pintype "passive"))
    )
    (net (code "66") (name "Net-(Q13-G)") (class "Default")
      (node (ref "Q13") (pin "1") (pinfunction "G_1") (pintype "passive"))
      (node (ref "R35") (pin "2") (pinfunction "2_2") (pintype "passive"))
      (node (ref "R36") (pin "1") (pinfunction "1_1") (pintype "passive"))
    )
    (net (code "67") (name "Net-(Q14-D)") (class "Default")
      (node (ref "D15") (pin "A") (pinfunction "A_A") (pintype "passive"))
      (node (ref "JP5") (pin "5") (pinfunction "5_5") (pintype "passive"))
      (node (ref "Q14") (pin "3") (pinfunction "D_3") (pintype "passive"))
      (node (ref "R48") (pin "2") (pinfunction "2_2") (pintype "passive"))
    )
    (net (code "68") (name "Net-(Q14-G)") (class "Default")
      (node (ref "Q14") (pin "1") (pinfunction "G_1") (pintype "passive"))
      (node (ref "R37") (pin "2") (pinfunction "2_2") (pintype "passive"))
      (node (ref "R38") (pin "1") (pinfunction "1_1") (pintype "passive"))
    )
    (net (code "69") (name "Net-(Q15-D)") (class "Default")
      (node (ref "D16") (pin "A") (pinfunction "A_A") (pintype "passive"))
      (node (ref "JP5") (pin "3") (pinfunction "3_3") (pintype "passive"))
      (node (ref "Q15") (pin "3") (pinfunction "D_3") (pintype "passive"))
      (node (ref "R49") (pin "2") (pinfunction "2_2") (pintype "passive"))
    )
    (net (code "70") (name "Net-(Q15-G)") (class "Default")
      (node (ref "Q15") (pin "1") (pinfunction "G_1") (pintype "passive"))
      (node (ref "R39") (pin "2") (pinfunction "2_2") (pintype "passive"))
      (node (ref "R40") (pin "1") (pinfunction "1_1") (pintype "passive"))
    )
    (net (code "71") (name "Net-(Q16-D)") (class "Default")
      (node (ref "D17") (pin "A") (pinfunction "A_A") (pintype "passive"))
      (node (ref "JP5") (pin "1") (pinfunction "1_1") (pintype "passive"))
      (node (ref "Q16") (pin "3") (pinfunction "D_3") (pintype "passive"))
      (node (ref "R50") (pin "2") (pinfunction "2_2") (pintype "passive"))
    )
    (net (code "72") (name "Net-(Q16-G)") (class "Default")
      (node (ref "Q16") (pin "1") (pinfunction "G_1") (pintype "passive"))
      (node (ref "R41") (pin "2") (pinfunction "2_2") (pintype "passive"))
      (node (ref "R42") (pin "1") (pinfunction "1_1") (pintype "passive"))
    )
    (net (code "73") (name "Net-(R54-Pad2)") (class "Default")
      (node (ref "R54") (pin "2") (pinfunction "2_2") (pintype "passive"))
      (node (ref "SJ3") (pin "1") (pinfunction "1_1") (pintype "passive"))
    )
    (net (code "74") (name "Net-(R55-Pad2)") (class "Default")
      (node (ref "R55") (pin "2") (pinfunction "2_2") (pintype "passive"))
      (node (ref "SJ3") (pin "3") (pinfunction "3_3") (pintype "passive"))
    )
    (net (code "75") (name "RESET") (class "Default")
      (node (ref "IC1") (pin "18") (pinfunction "~{RESET}_18") (pintype "input"))
      (node (ref "S1") (pin "3") (pinfunction "3_3") (pintype "passive"))
      (node (ref "S1") (pin "4") (pinfunction "4_4") (pintype "passive"))
    )
    (net (code "76") (name "SCL") (class "Default")
      (node (ref "IC1") (pin "12") (pinfunction "SCL_12") (pintype "input"))
      (node (ref "R55") (pin "1") (pinfunction "1_1") (pintype "passive"))
    )
    (net (code "77") (name "SDA") (class "Default")
      (node (ref "IC1") (pin "13") (pinfunction "SDA_13") (pintype "bidirectional"))
      (node (ref "R54") (pin "1") (pinfunction "1_1") (pintype "passive"))
    )
    (net (code "78") (name "VCC") (class "Default")
      (node (ref "IC1") (pin "9") (pinfunction "VDD_9") (pintype "power_in"))
      (node (ref "J6") (pin "1") (pinfunction "1_1") (pintype "passive"))
      (node (ref "J6") (pin "3") (pinfunction "3_3") (pintype "passive"))
      (node (ref "J6") (pin "5") (pinfunction "5_5") (pintype "passive"))
      (node (ref "R26") (pin "2") (pinfunction "2_2") (pintype "passive"))
      (node (ref "SJ3") (pin "2") (pinfunction "2_2") (pintype "passive"))
    )
    (net (code "79") (name "unconnected-(IC1-INTA-Pad20)") (class "Default")
      (node (ref "IC1") (pin "20") (pinfunction "INTA_20") (pintype "output"))
    )
    (net (code "80") (name "unconnected-(IC1-INTB-Pad19)") (class "Default")
      (node (ref "IC1") (pin "19") (pinfunction "INTB_19") (pintype "output"))
    )
  )
)
